# Controller.net
KiCad netlist of a schematic drawn in Altium Designer
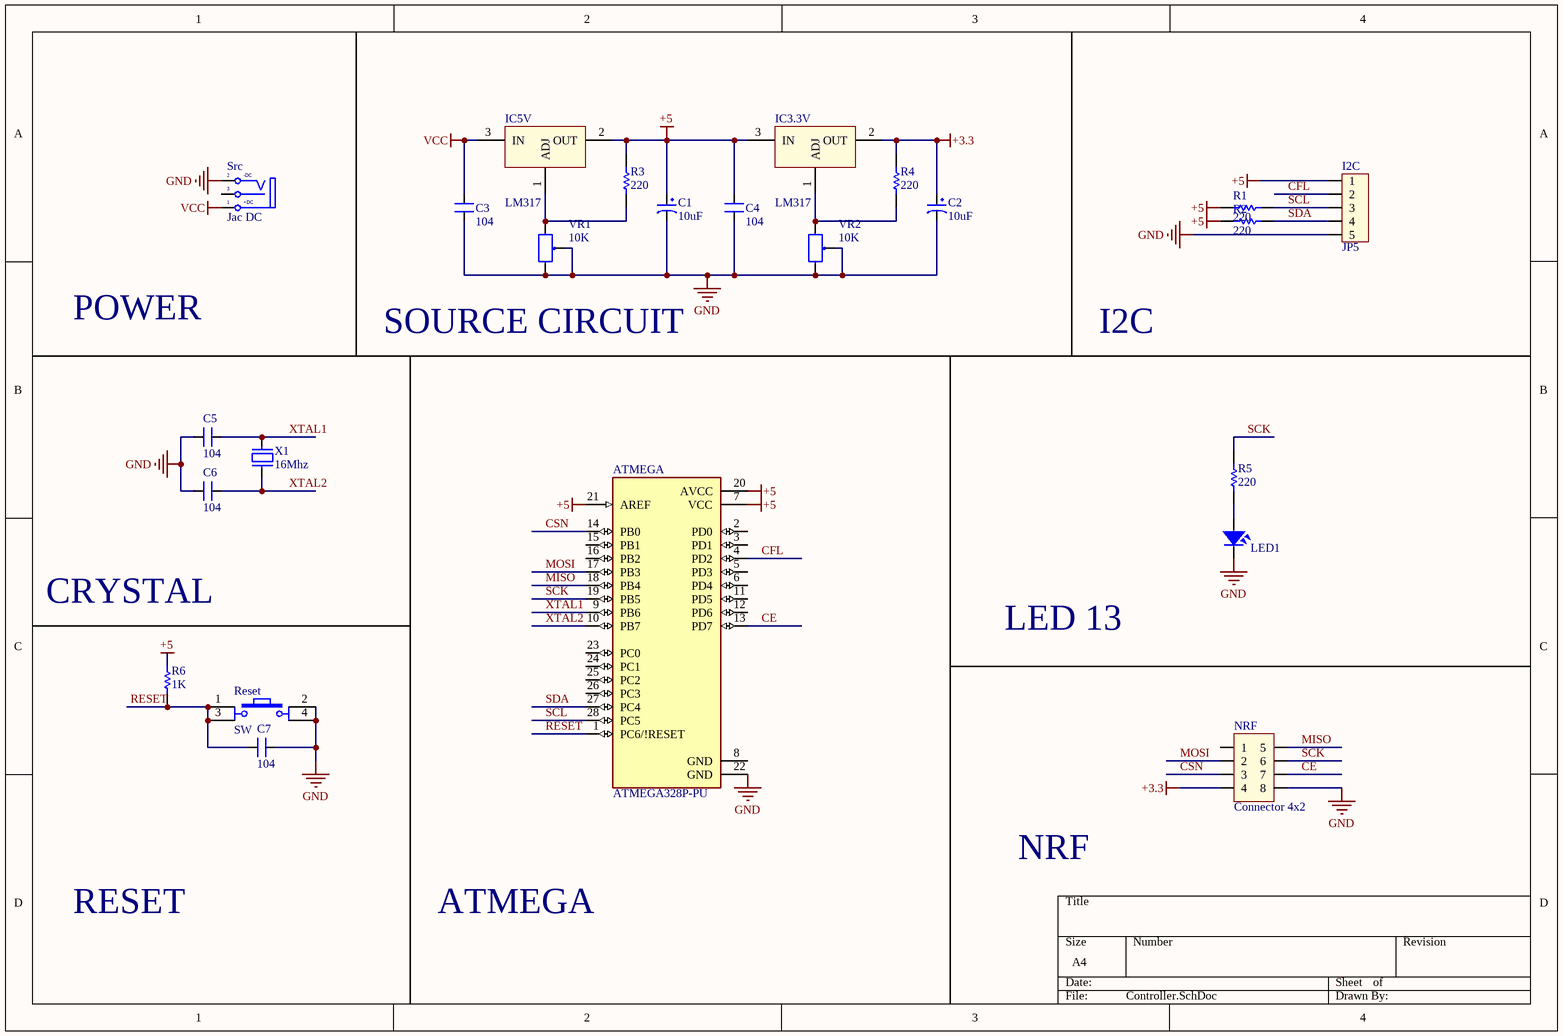
[diagram p0: Controller.SchDoc]

(export (version "E")
  (design (tool "Eeschema 10.0.6"))
  (components
    (comp (ref "ATMEGA")
      (value "ATMEGA328P-PU")
      (footprint "DIP794W46P254L2967H457Q28B")
      (description "AVR AVRÂ® ATmega Microcontroller IC 8-Bit 20MHz 32KB _16K x 16_ FLASH 28-PDIP")
      (fields (field (name "MF") "Microchip"))
      (libsource (lib "ATMEGA328P-PU") (part "ATMEGA328P-PU"))
    )
    (comp (ref "C1")
      (value "10uF")
      (footprint "CP1/2")
      (description "Cap P  0,1uF < 22uF , 16 - 50V")
      (libsource (lib "syhaunguyen__1") (part "CP1"))
    )
    (comp (ref "C2")
      (value "10uF")
      (footprint "CP1/2")
      (description "Cap P  0,1uF < 22uF , 16 - 50V")
      (libsource (lib "syhaunguyen__1") (part "CP1"))
    )
    (comp (ref "C3")
      (value "104")
      (footprint "CN2")
      (description "Cap np 104 => 105pF")
      (libsource (lib "syhaunguyen__1") (part "CN2"))
    )
    (comp (ref "C4")
      (value "104")
      (footprint "CN2")
      (description "Cap np 104 => 105pF")
      (libsource (lib "syhaunguyen__1") (part "CN2"))
    )
    (comp (ref "C5")
      (value "104")
      (footprint "CN2")
      (description "Cap np 104 => 105pF")
      (libsource (lib "syhaunguyen__1") (part "CN2"))
    )
    (comp (ref "C6")
      (value "104")
      (footprint "CN2")
      (description "Cap np 104 => 105pF")
      (libsource (lib "syhaunguyen__1") (part "CN2"))
    )
    (comp (ref "C7")
      (value "104")
      (footprint "CN2")
      (description "Cap np 104 => 105pF")
      (libsource (lib "syhaunguyen__1") (part "CN2"))
    )
    (comp (ref "I2C")
      (value "JP5")
      (footprint "CON5")
      (description "Connector 5")
      (libsource (lib "syhaunguyen__1") (part "Con5"))
    )
    (comp (ref "IC3.3V")
      (value "LM317")
      (footprint "QTO-220")
      (description "Adj Voltage +1.2 -> +37V")
      (libsource (lib "syhaunguyen__1") (part "LM317"))
    )
    (comp (ref "IC5V")
      (value "LM317")
      (footprint "QTO-220")
      (description "Adj Voltage +1.2 -> +37V")
      (libsource (lib "syhaunguyen__1") (part "LM317"))
    )
    (comp (ref "LED1")
      (value "LED")
      (footprint "LED-5-Green")
      (description "LED Single colour Green and Red")
      (libsource (lib "syhaunguyen__1") (part "LED"))
    )
    (comp (ref "NRF")
      (value "Connector 4x2")
      (footprint "JP4x2")
      (libsource (lib "syhaunguyen__1") (part "JP4x2"))
    )
    (comp (ref "R1")
      (value "220")
      (footprint "R1/4W")
      (description "Resistor")
      (fields
        (field (name "MANUFACTURER") "Generic Components")
        (field (name "Comment") "Res1")
        (field (name "PUBLISHER") "Altium Hobart Technology Centre")
      )
      (libsource (lib "syhaunguyen__1") (part "Res1_1"))
    )
    (comp (ref "R2")
      (value "220")
      (footprint "R1/4W")
      (description "Resistor")
      (fields
        (field (name "MANUFACTURER") "Generic Components")
        (field (name "Comment") "Res1")
        (field (name "PUBLISHER") "Altium Hobart Technology Centre")
      )
      (libsource (lib "syhaunguyen__1") (part "Res1_1"))
    )
    (comp (ref "R3")
      (value "220")
      (footprint "R1/4W")
      (description "Resistor")
      (fields
        (field (name "MANUFACTURER") "Generic Components")
        (field (name "Comment") "Res1")
        (field (name "PUBLISHER") "Altium Hobart Technology Centre")
      )
      (libsource (lib "syhaunguyen__1") (part "Res1_1"))
    )
    (comp (ref "R4")
      (value "220")
      (footprint "R1/4W")
      (description "Resistor")
      (fields
        (field (name "MANUFACTURER") "Generic Components")
        (field (name "Comment") "Res1")
        (field (name "PUBLISHER") "Altium Hobart Technology Centre")
      )
      (libsource (lib "syhaunguyen__1") (part "Res1_1"))
    )
    (comp (ref "R5")
      (value "220")
      (footprint "R1/4W")
      (description "Resistor")
      (fields
        (field (name "MANUFACTURER") "Generic Components")
        (field (name "Comment") "Res1")
        (field (name "PUBLISHER") "Altium Hobart Technology Centre")
      )
      (libsource (lib "syhaunguyen__1") (part "Res1_1"))
    )
    (comp (ref "R6")
      (value "1K")
      (footprint "R1/4W")
      (description "Resistor")
      (fields
        (field (name "MANUFACTURER") "Generic Components")
        (field (name "Comment") "Res1")
        (field (name "PUBLISHER") "Altium Hobart Technology Centre")
      )
      (libsource (lib "syhaunguyen__1") (part "Res1_1"))
    )
    (comp (ref "Reset")
      (value "SW")
      (footprint "SW4")
      (description "Switch button 4 pin")
      (libsource (lib "syhaunguyen__1") (part "SW4"))
    )
    (comp (ref "Src")
      (value "Jac DC")
      (footprint "DC-IN")
      (description "Jac DC input")
      (libsource (lib "syhaunguyen__1") (part "DCIN"))
    )
    (comp (ref "VR1")
      (value "10K")
      (footprint "VR")
      (description "Var Resistor")
      (libsource (lib "syhaunguyen__1") (part "VR"))
    )
    (comp (ref "VR2")
      (value "10K")
      (footprint "VR")
      (description "Var Resistor")
      (libsource (lib "syhaunguyen__1") (part "VR"))
    )
    (comp (ref "X1")
      (value "16Mhz")
      (footprint "XT2")
      (description "Crystal For all Crystal 2pin.")
      (libsource (lib "syhaunguyen__1") (part "XT2"))
    )
  )
  (nets
    (net (code "1") (name "+3.3") (class "Default")
      (node (ref "C2") (pin "1") (pinfunction "1_1") (pintype "passive"))
      (node (ref "IC3.3V") (pin "2") (pinfunction "OUT_2") (pintype "passive"))
      (node (ref "NRF") (pin "4") (pinfunction "4_4") (pintype "passive"))
      (node (ref "R4") (pin "1") (pinfunction "1_1") (pintype "passive"))
    )
    (net (code "2") (name "+5") (class "Default")
      (node (ref "ATMEGA") (pin "20") (pinfunction "AVCC_20") (pintype "power_in"))
      (node (ref "ATMEGA") (pin "21") (pinfunction "AREF_21") (pintype "input"))
      (node (ref "ATMEGA") (pin "7") (pinfunction "VCC_7") (pintype "power_in"))
      (node (ref "C1") (pin "1") (pinfunction "1_1") (pintype "passive"))
      (node (ref "C4") (pin "2") (pinfunction "2_2") (pintype "passive"))
      (node (ref "I2C") (pin "1") (pinfunction "1_1") (pintype "passive"))
      (node (ref "IC3.3V") (pin "3") (pinfunction "IN_3") (pintype "passive"))
      (node (ref "IC5V") (pin "2") (pinfunction "OUT_2") (pintype "passive"))
      (node (ref "R1") (pin "1") (pinfunction "1_1") (pintype "passive"))
      (node (ref "R2") (pin "1") (pinfunction "1_1") (pintype "passive"))
      (node (ref "R3") (pin "1") (pinfunction "1_1") (pintype "passive"))
      (node (ref "R6") (pin "2") (pinfunction "2_2") (pintype "passive"))
    )
    (net (code "3") (name "/CE") (class "Default")
      (node (ref "ATMEGA") (pin "13") (pinfunction "PD7_13") (pintype "bidirectional"))
      (node (ref "NRF") (pin "7") (pinfunction "7_7") (pintype "passive"))
    )
    (net (code "4") (name "/CFL") (class "Default")
      (node (ref "ATMEGA") (pin "4") (pinfunction "PD2_4") (pintype "bidirectional"))
      (node (ref "I2C") (pin "2") (pinfunction "2_2") (pintype "passive"))
    )
    (net (code "5") (name "/CSN") (class "Default")
      (node (ref "ATMEGA") (pin "14") (pinfunction "PB0_14") (pintype "bidirectional"))
      (node (ref "NRF") (pin "3") (pinfunction "3_3") (pintype "passive"))
    )
    (net (code "6") (name "/MISO") (class "Default")
      (node (ref "ATMEGA") (pin "18") (pinfunction "PB4_18") (pintype "bidirectional"))
      (node (ref "NRF") (pin "5") (pinfunction "5_5") (pintype "passive"))
    )
    (net (code "7") (name "/MOSI") (class "Default")
      (node (ref "ATMEGA") (pin "17") (pinfunction "PB3_17") (pintype "bidirectional"))
      (node (ref "NRF") (pin "2") (pinfunction "2_2") (pintype "passive"))
    )
    (net (code "8") (name "/RESET") (class "Default")
      (node (ref "ATMEGA") (pin "1") (pinfunction "PC6/!RESET_1") (pintype "bidirectional"))
      (node (ref "C7") (pin "1") (pinfunction "1_1") (pintype "passive"))
      (node (ref "R6") (pin "1") (pinfunction "1_1") (pintype "passive"))
      (node (ref "Reset") (pin "1") (pintype "passive"))
      (node (ref "Reset") (pin "3") (pintype "passive"))
    )
    (net (code "9") (name "/SCK") (class "Default")
      (node (ref "ATMEGA") (pin "19") (pinfunction "PB5_19") (pintype "bidirectional"))
      (node (ref "NRF") (pin "6") (pinfunction "6_6") (pintype "passive"))
      (node (ref "R5") (pin "1") (pinfunction "1_1") (pintype "passive"))
    )
    (net (code "10") (name "/SCL") (class "Default")
      (node (ref "ATMEGA") (pin "28") (pinfunction "PC5_28") (pintype "bidirectional"))
      (node (ref "I2C") (pin "3") (pinfunction "3_3") (pintype "passive"))
      (node (ref "R1") (pin "2") (pinfunction "2_2") (pintype "passive"))
    )
    (net (code "11") (name "/SDA") (class "Default")
      (node (ref "ATMEGA") (pin "27") (pinfunction "PC4_27") (pintype "bidirectional"))
      (node (ref "I2C") (pin "4") (pinfunction "4_4") (pintype "passive"))
      (node (ref "R2") (pin "2") (pinfunction "2_2") (pintype "passive"))
    )
    (net (code "12") (name "/XTAL1") (class "Default")
      (node (ref "ATMEGA") (pin "9") (pinfunction "PB6_9") (pintype "bidirectional"))
      (node (ref "C5") (pin "2") (pinfunction "2_2") (pintype "passive"))
      (node (ref "X1") (pin "2") (pinfunction "2_2") (pintype "passive"))
    )
    (net (code "13") (name "/XTAL2") (class "Default")
      (node (ref "ATMEGA") (pin "10") (pinfunction "PB7_10") (pintype "bidirectional"))
      (node (ref "C6") (pin "2") (pinfunction "2_2") (pintype "passive"))
      (node (ref "X1") (pin "1") (pinfunction "1_1") (pintype "passive"))
    )
    (net (code "14") (name "GND") (class "Default")
      (node (ref "ATMEGA") (pin "22") (pinfunction "GND_22") (pintype "power_in"))
      (node (ref "C1") (pin "2") (pinfunction "2_2") (pintype "passive"))
      (node (ref "C2") (pin "2") (pinfunction "2_2") (pintype "passive"))
      (node (ref "C3") (pin "1") (pinfunction "1_1") (pintype "passive"))
      (node (ref "C4") (pin "1") (pinfunction "1_1") (pintype "passive"))
      (node (ref "C5") (pin "1") (pinfunction "1_1") (pintype "passive"))
      (node (ref "C6") (pin "1") (pinfunction "1_1") (pintype "passive"))
      (node (ref "C7") (pin "2") (pinfunction "2_2") (pintype "passive"))
      (node (ref "I2C") (pin "5") (pinfunction "5_5") (pintype "passive"))
      (node (ref "LED1") (pin "2") (pinfunction "2_2") (pintype "passive"))
      (node (ref "NRF") (pin "8") (pinfunction "8_8") (pintype "passive"))
      (node (ref "Reset") (pin "2") (pintype "passive"))
      (node (ref "Reset") (pin "4") (pintype "passive"))
      (node (ref "Src") (pin "2") (pinfunction "TN_2") (pintype "passive"))
      (node (ref "VR1") (pin "2") (pinfunction "2_2") (pintype "passive"))
      (node (ref "VR1") (pin "3") (pinfunction "3_3") (pintype "passive"))
      (node (ref "VR2") (pin "2") (pinfunction "2_2") (pintype "passive"))
      (node (ref "VR2") (pin "3") (pinfunction "3_3") (pintype "passive"))
    )
    (net (code "15") (name "Net-(IC3.3V-ADJ)") (class "Default")
      (node (ref "IC3.3V") (pin "1") (pinfunction "ADJ_1") (pintype "passive"))
      (node (ref "R4") (pin "2") (pinfunction "2_2") (pintype "passive"))
      (node (ref "VR2") (pin "1") (pinfunction "1_1") (pintype "passive"))
    )
    (net (code "16") (name "Net-(IC5V-ADJ)") (class "Default")
      (node (ref "IC5V") (pin "1") (pinfunction "ADJ_1") (pintype "passive"))
      (node (ref "R3") (pin "2") (pinfunction "2_2") (pintype "passive"))
      (node (ref "VR1") (pin "1") (pinfunction "1_1") (pintype "passive"))
    )
    (net (code "17") (name "Net-(LED1-Pad1)") (class "Default")
      (node (ref "LED1") (pin "1") (pinfunction "1_1") (pintype "passive"))
      (node (ref "R5") (pin "2") (pinfunction "2_2") (pintype "passive"))
    )
    (net (code "18") (name "VCC") (class "Default")
      (node (ref "C3") (pin "2") (pinfunction "2_2") (pintype "passive"))
      (node (ref "IC5V") (pin "3") (pinfunction "IN_3") (pintype "passive"))
      (node (ref "Src") (pin "1") (pinfunction "T_1") (pintype "passive"))
    )
    (net (code "19") (name "unconnected-(ATMEGA-GND-Pad8)") (class "Default")
      (node (ref "ATMEGA") (pin "8") (pinfunction "GND_8") (pintype "power_in"))
    )
    (net (code "20") (name "unconnected-(ATMEGA-PB1-Pad15)") (class "Default")
      (node (ref "ATMEGA") (pin "15") (pinfunction "PB1_15") (pintype "bidirectional"))
    )
    (net (code "21") (name "unconnected-(ATMEGA-PB2-Pad16)") (class "Default")
      (node (ref "ATMEGA") (pin "16") (pinfunction "PB2_16") (pintype "bidirectional"))
    )
    (net (code "22") (name "unconnected-(ATMEGA-PC0-Pad23)") (class "Default")
      (node (ref "ATMEGA") (pin "23") (pinfunction "PC0_23") (pintype "bidirectional"))
    )
    (net (code "23") (name "unconnected-(ATMEGA-PC1-Pad24)") (class "Default")
      (node (ref "ATMEGA") (pin "24") (pinfunction "PC1_24") (pintype "bidirectional"))
    )
    (net (code "24") (name "unconnected-(ATMEGA-PC2-Pad25)") (class "Default")
      (node (ref "ATMEGA") (pin "25") (pinfunction "PC2_25") (pintype "bidirectional"))
    )
    (net (code "25") (name "unconnected-(ATMEGA-PC3-Pad26)") (class "Default")
      (node (ref "ATMEGA") (pin "26") (pinfunction "PC3_26") (pintype "bidirectional"))
    )
    (net (code "26") (name "unconnected-(ATMEGA-PD0-Pad2)") (class "Default")
      (node (ref "ATMEGA") (pin "2") (pinfunction "PD0_2") (pintype "bidirectional"))
    )
    (net (code "27") (name "unconnected-(ATMEGA-PD1-Pad3)") (class "Default")
      (node (ref "ATMEGA") (pin "3") (pinfunction "PD1_3") (pintype "bidirectional"))
    )
    (net (code "28") (name "unconnected-(ATMEGA-PD3-Pad5)") (class "Default")
      (node (ref "ATMEGA") (pin "5") (pinfunction "PD3_5") (pintype "bidirectional"))
    )
    (net (code "29") (name "unconnected-(ATMEGA-PD4-Pad6)") (class "Default")
      (node (ref "ATMEGA") (pin "6") (pinfunction "PD4_6") (pintype "bidirectional"))
    )
    (net (code "30") (name "unconnected-(ATMEGA-PD5-Pad11)") (class "Default")
      (node (ref "ATMEGA") (pin "11") (pinfunction "PD5_11") (pintype "bidirectional"))
    )
    (net (code "31") (name "unconnected-(ATMEGA-PD6-Pad12)") (class "Default")
      (node (ref "ATMEGA") (pin "12") (pinfunction "PD6_12") (pintype "bidirectional"))
    )
    (net (code "32") (name "unconnected-(NRF-Pad1)") (class "Default")
      (node (ref "NRF") (pin "1") (pinfunction "1_1") (pintype "passive"))
    )
    (net (code "33") (name "unconnected-(Src-S-Pad3)") (class "Default")
      (node (ref "Src") (pin "3") (pinfunction "S_3") (pintype "power_in"))
    )
  )
)
